# JLCPCB_MEG_SCHEM.net
KiCad netlist of a schematic drawn in EasyEDA
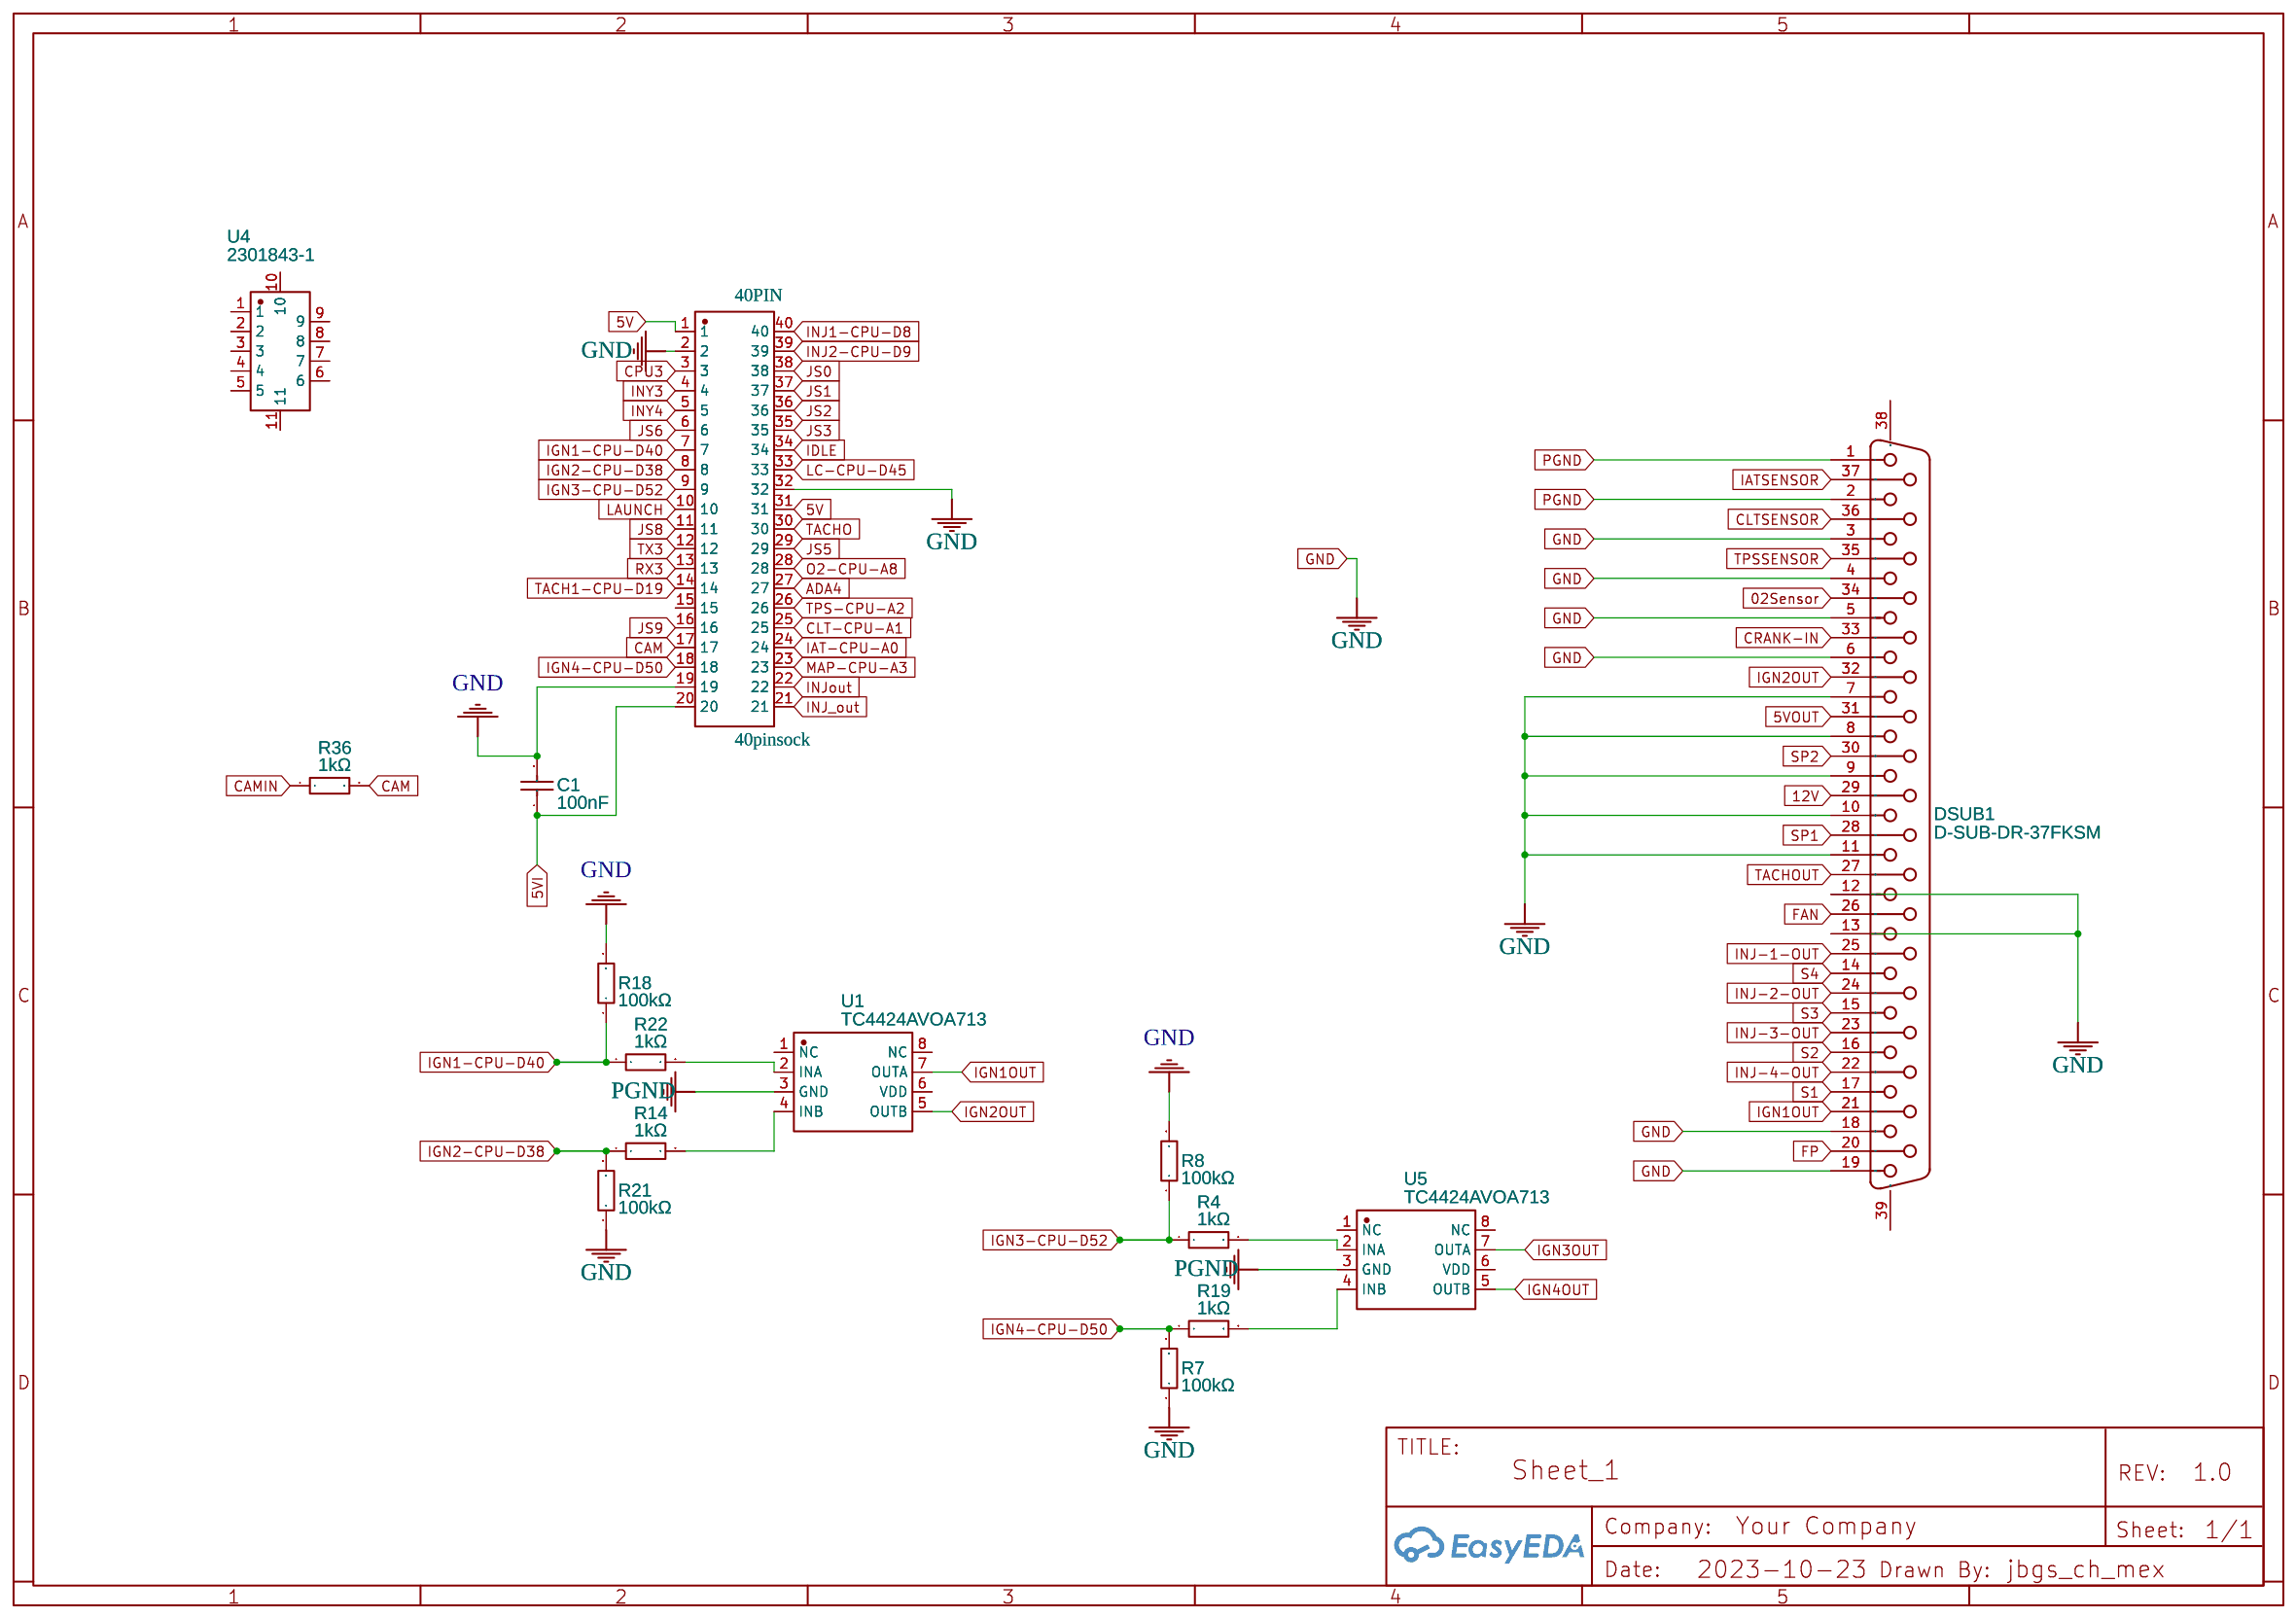
[diagram p0: Sheet_1]
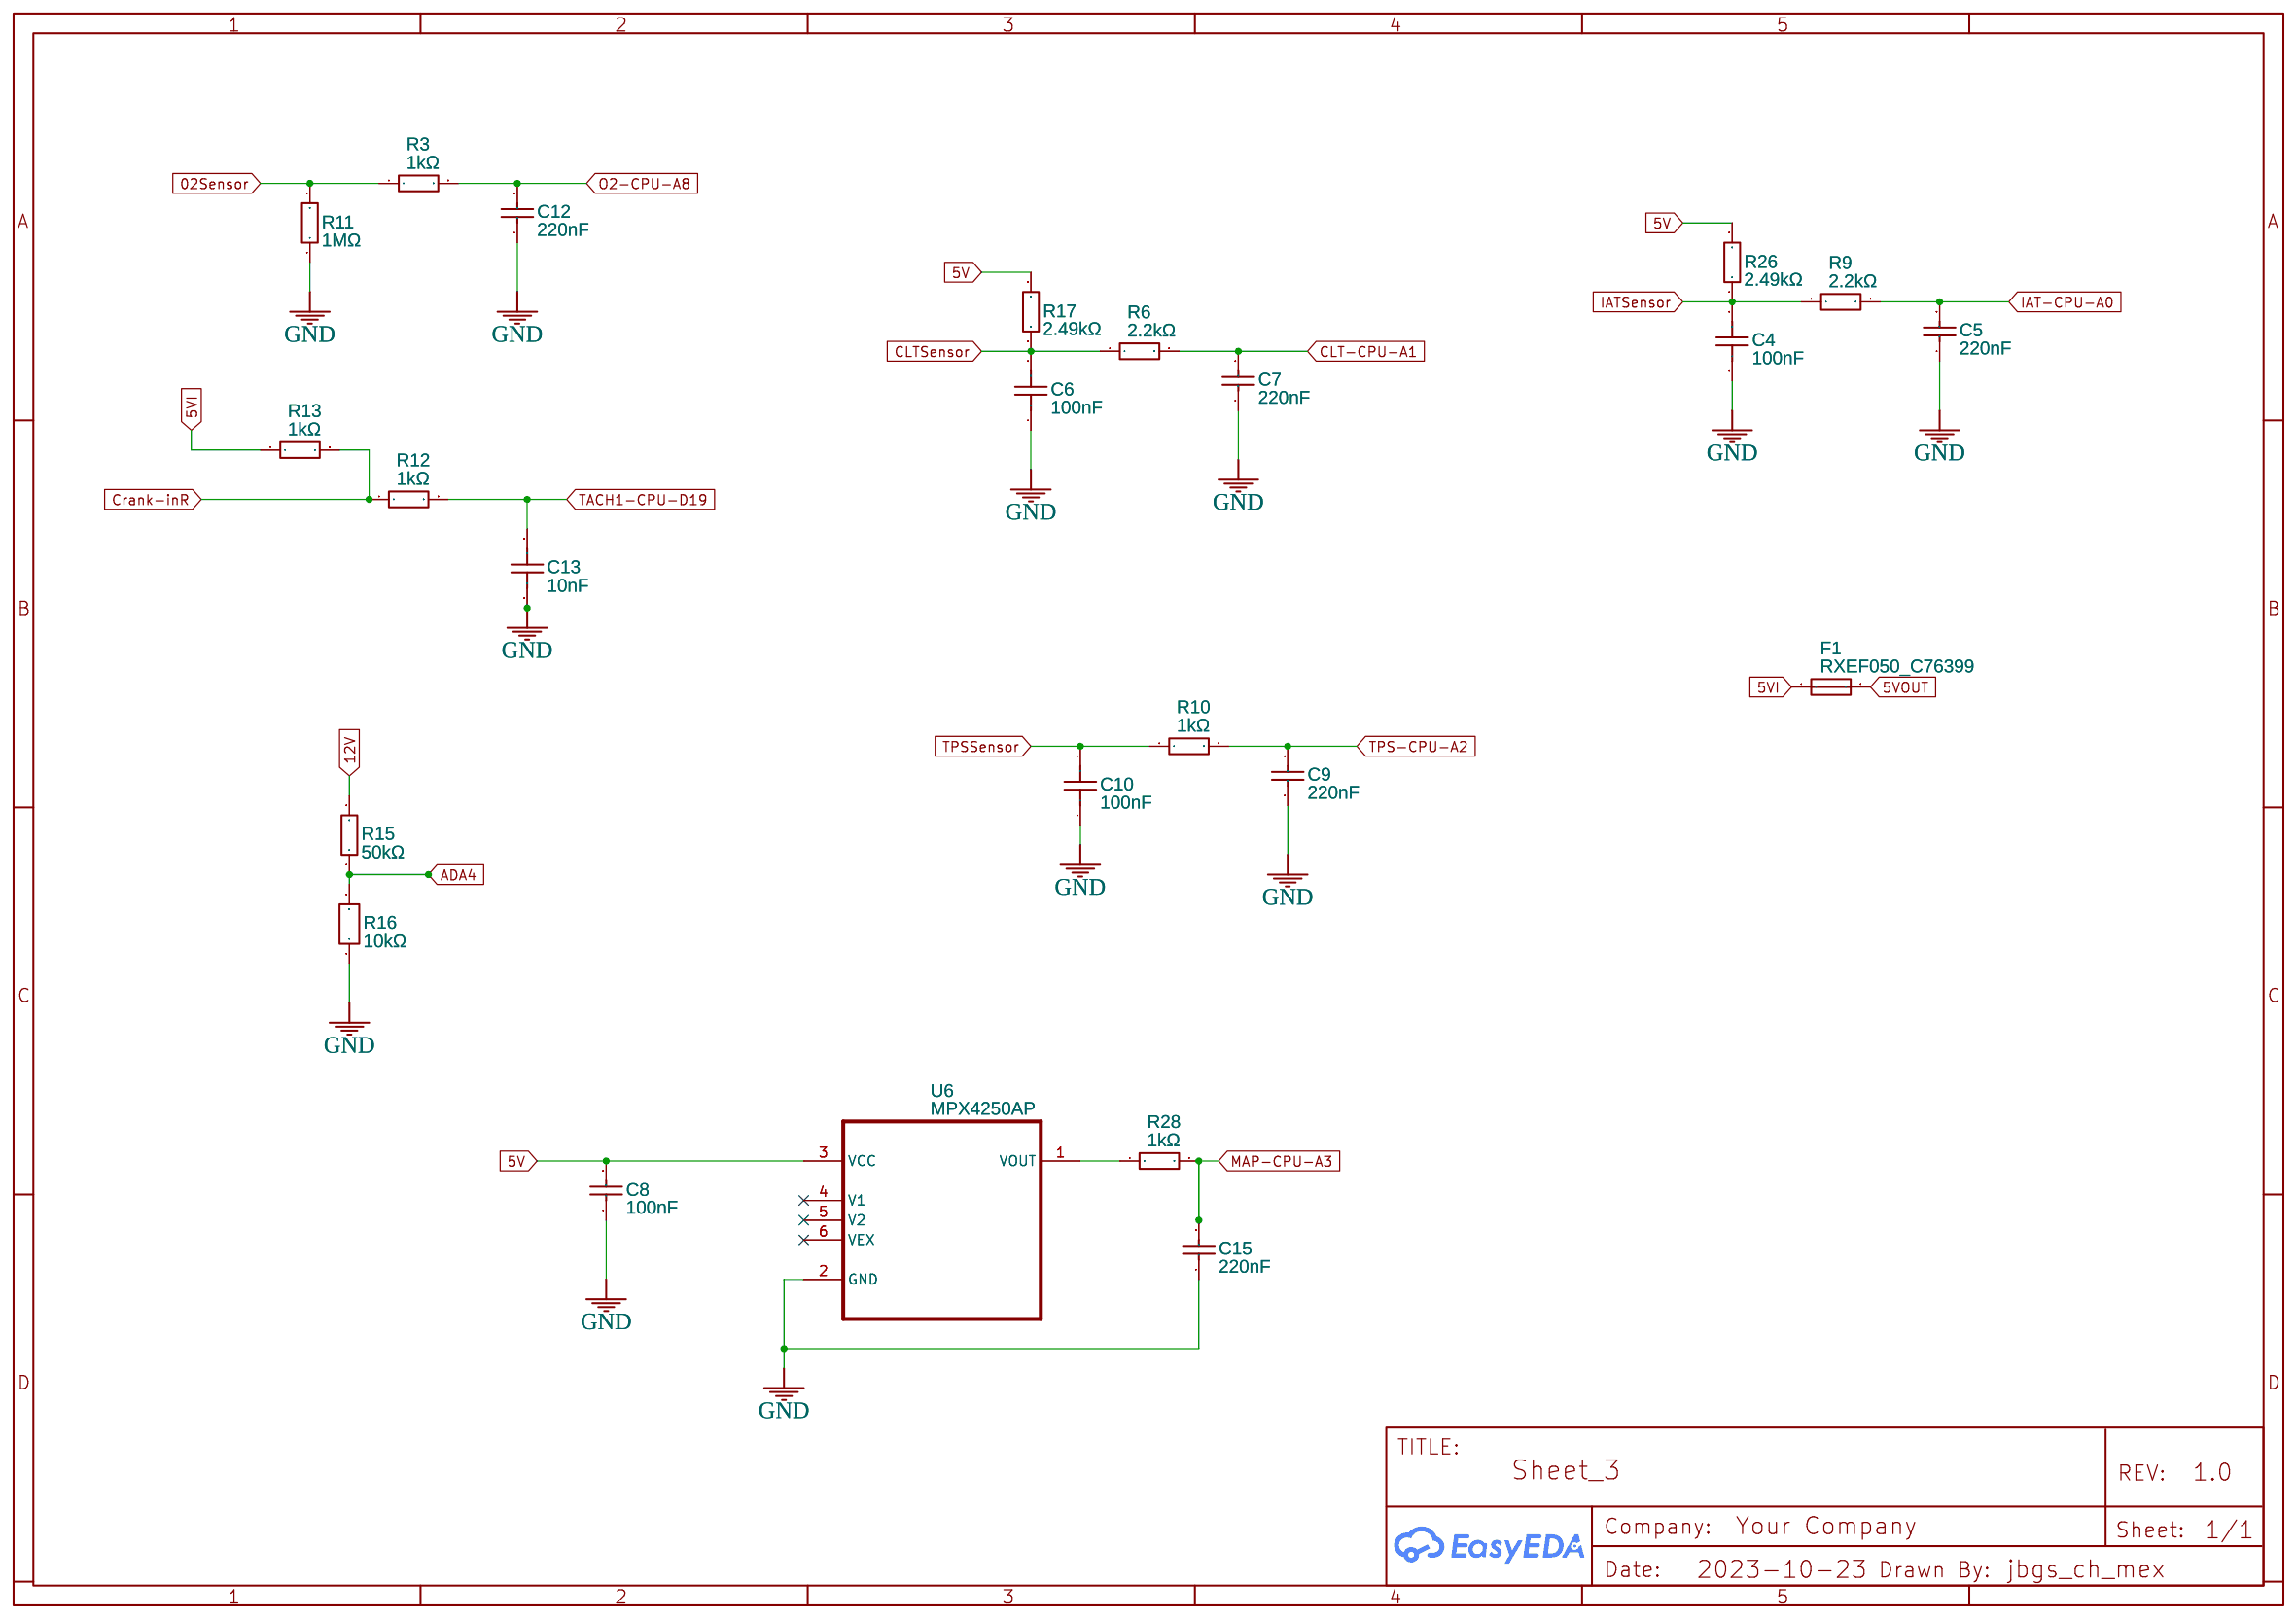
[diagram p1: Sheet_3]
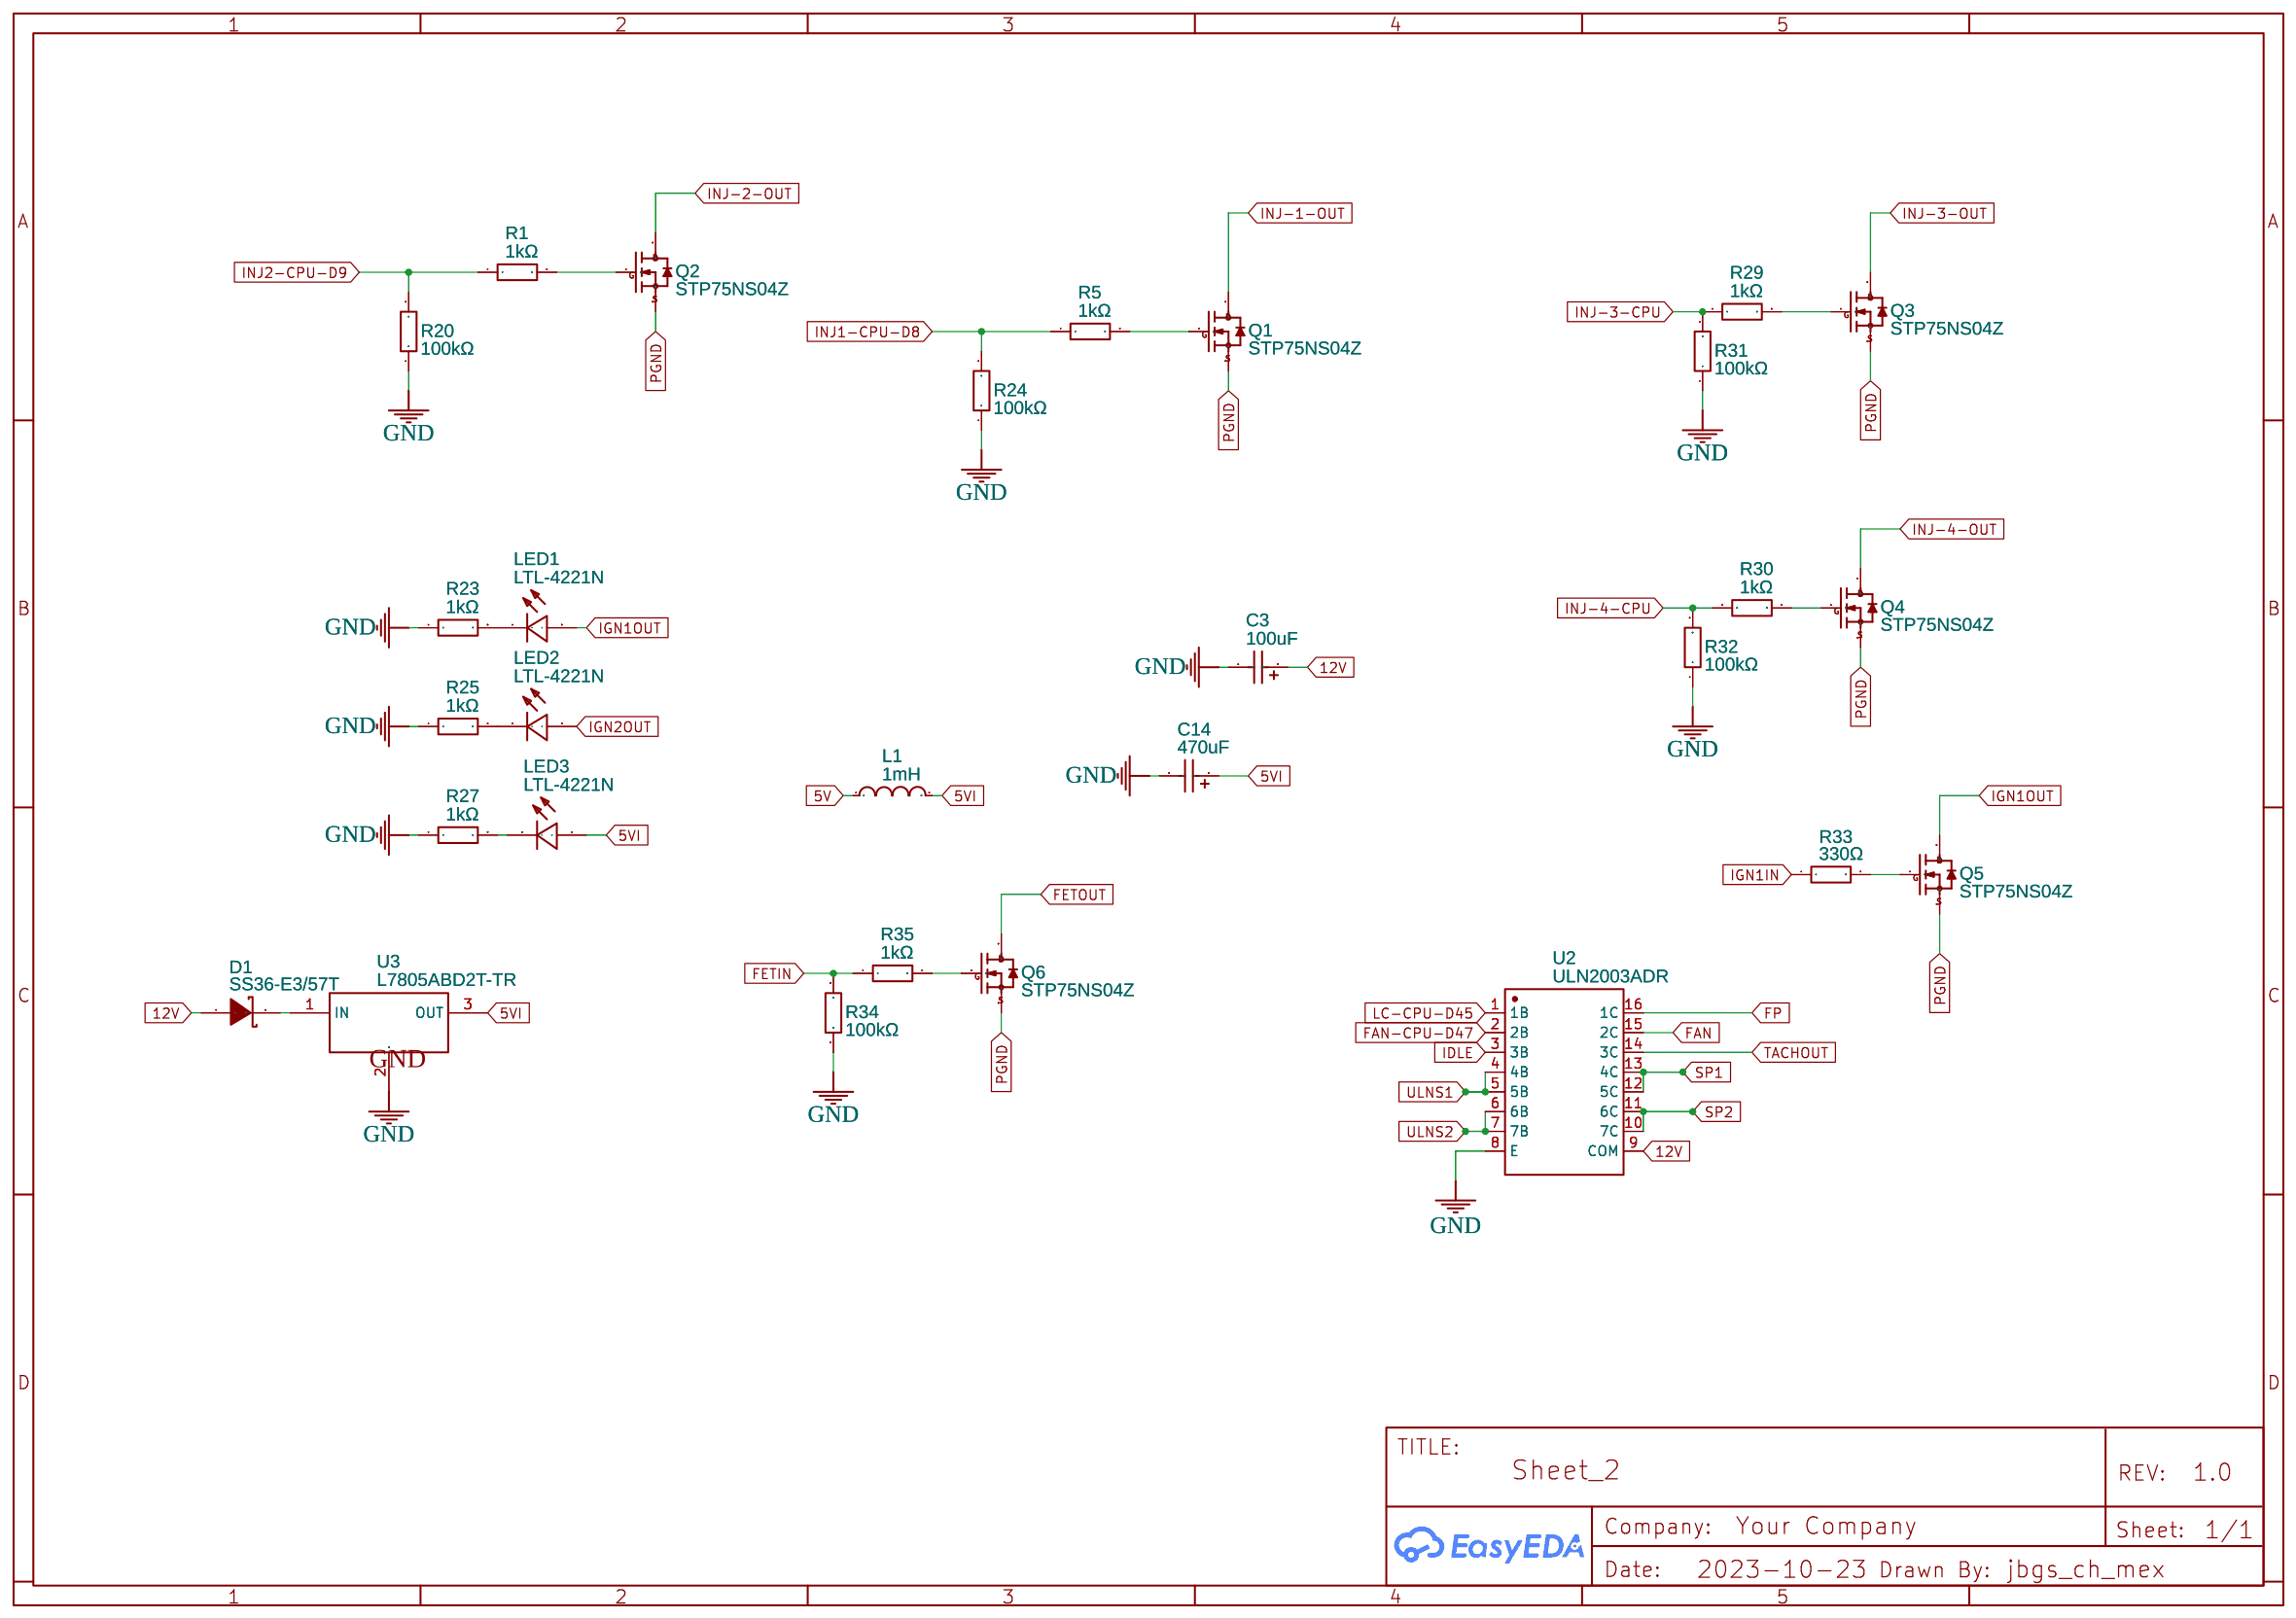
[diagram p2: Sheet_2]

(export (version "E")
  (design (tool "Eeschema 10.0.6"))
  (components
    (comp (ref "40PIN") (value "40pinsock") (libsource (lib "") (part "Unknown_365_-550")))
    (comp (ref "C1")
      (value "100nF")
      (fields
        (field (name "Manufacturer Part") "CC0805KRX7R9BB104")
        (field (name "Manufacturer") "YAGEO(国巨)")
      )
      (libsource (lib "") (part "CC0805KRX7R9BB104"))
    )
    (comp (ref "DSUB1")
      (value "D-SUB-DR-37FKSM")
      (fields (field (name "Manufacturer") "ZHOURI(洲日)"))
      (libsource (lib "") (part "D-SUB-DR-37FKSM"))
    )
    (comp (ref "R4")
      (value "1kΩ")
      (fields
        (field (name "Manufacturer Part") "0603WAF1001T5E")
        (field (name "Manufacturer") "UNI-ROYAL(厚声)")
      )
      (libsource (lib "") (part "0603WAF1001T5E"))
    )
    (comp (ref "R7")
      (value "100kΩ")
      (fields
        (field (name "Manufacturer Part") "0603WAF1003T5E")
        (field (name "Manufacturer") "UNI-ROYAL(厚声)")
      )
      (libsource (lib "") (part "0603WAF1003T5E"))
    )
    (comp (ref "R8")
      (value "100kΩ")
      (fields
        (field (name "Manufacturer Part") "0603WAF1003T5E")
        (field (name "Manufacturer") "UNI-ROYAL(厚声)")
      )
      (libsource (lib "") (part "0603WAF1003T5E"))
    )
    (comp (ref "R14")
      (value "1kΩ")
      (fields
        (field (name "Manufacturer Part") "0603WAF1001T5E")
        (field (name "Manufacturer") "UNI-ROYAL(厚声)")
      )
      (libsource (lib "") (part "0603WAF1001T5E"))
    )
    (comp (ref "R18")
      (value "100kΩ")
      (fields
        (field (name "Manufacturer Part") "0603WAF1003T5E")
        (field (name "Manufacturer") "UNI-ROYAL(厚声)")
      )
      (libsource (lib "") (part "0603WAF1003T5E"))
    )
    (comp (ref "R19")
      (value "1kΩ")
      (fields
        (field (name "Manufacturer Part") "0603WAF1001T5E")
        (field (name "Manufacturer") "UNI-ROYAL(厚声)")
      )
      (libsource (lib "") (part "0603WAF1001T5E"))
    )
    (comp (ref "R21")
      (value "100kΩ")
      (fields
        (field (name "Manufacturer Part") "0603WAF1003T5E")
        (field (name "Manufacturer") "UNI-ROYAL(厚声)")
      )
      (libsource (lib "") (part "0603WAF1003T5E"))
    )
    (comp (ref "R22")
      (value "1kΩ")
      (fields
        (field (name "Manufacturer Part") "0603WAF1001T5E")
        (field (name "Manufacturer") "UNI-ROYAL(厚声)")
      )
      (libsource (lib "") (part "0603WAF1001T5E"))
    )
    (comp (ref "R36")
      (value "1kΩ")
      (fields
        (field (name "Manufacturer Part") "0603WAF1001T5E")
        (field (name "Manufacturer") "UNI-ROYAL(厚声)")
      )
      (libsource (lib "") (part "0603WAF1001T5E"))
    )
    (comp (ref "U1")
      (value "TC4424AVOA713")
      (fields (field (name "Manufacturer") "MICROCHIP(美国微芯)"))
      (libsource (lib "") (part "TC4424AVOA713"))
    )
    (comp (ref "U4")
      (value "2301843-1")
      (fields (field (name "Manufacturer") "TE Connectivity(美国泰科)"))
      (libsource (lib "") (part "2301843-1"))
    )
    (comp (ref "U5")
      (value "TC4424AVOA713")
      (fields (field (name "Manufacturer") "MICROCHIP(美国微芯)"))
      (libsource (lib "") (part "TC4424AVOA713"))
    )
    (comp (ref "C4")
      (value "100nF")
      (fields
        (field (name "Manufacturer Part") "CC0603KRX7R9BB104")
        (field (name "Manufacturer") "YAGEO(国巨)")
      )
      (libsource (lib "") (part "CC0603KRX7R9BB104"))
    )
    (comp (ref "C5")
      (value "220nF")
      (fields
        (field (name "Manufacturer Part") "CL10B224KA8NNNC")
        (field (name "Manufacturer") "SAMSUNG(三星)")
      )
      (libsource (lib "") (part "CL10B224KA8NNNC"))
    )
    (comp (ref "C6")
      (value "100nF")
      (fields
        (field (name "Manufacturer Part") "CC0603KRX7R9BB104")
        (field (name "Manufacturer") "YAGEO(国巨)")
      )
      (libsource (lib "") (part "CC0603KRX7R9BB104"))
    )
    (comp (ref "C7")
      (value "220nF")
      (fields
        (field (name "Manufacturer Part") "CL10B224KA8NNNC")
        (field (name "Manufacturer") "SAMSUNG(三星)")
      )
      (libsource (lib "") (part "CL10B224KA8NNNC"))
    )
    (comp (ref "C8")
      (value "100nF")
      (fields
        (field (name "Manufacturer Part") "CC0805KRX7R9BB104")
        (field (name "Manufacturer") "YAGEO(国巨)")
      )
      (libsource (lib "") (part "CC0805KRX7R9BB104"))
    )
    (comp (ref "C9")
      (value "220nF")
      (fields
        (field (name "Manufacturer Part") "CL10B224KA8NNNC")
        (field (name "Manufacturer") "SAMSUNG(三星)")
      )
      (libsource (lib "") (part "CL10B224KA8NNNC"))
    )
    (comp (ref "C10")
      (value "100nF")
      (fields
        (field (name "Manufacturer Part") "CC0603KRX7R9BB104")
        (field (name "Manufacturer") "YAGEO(国巨)")
      )
      (libsource (lib "") (part "CC0603KRX7R9BB104"))
    )
    (comp (ref "C12")
      (value "220nF")
      (fields
        (field (name "Manufacturer Part") "CL10B224KA8NNNC")
        (field (name "Manufacturer") "SAMSUNG(三星)")
      )
      (libsource (lib "") (part "CL10B224KA8NNNC"))
    )
    (comp (ref "C13")
      (value "10nF")
      (fields (field (name "Manufacturer Part") "C0805C103K1RAC7800") (field (name "Manufacturer") "KEMET"))
      (libsource (lib "") (part "C0805C103K1RAC7800"))
    )
    (comp (ref "C15")
      (value "220nF")
      (fields
        (field (name "Manufacturer Part") "CL10B224KA8NNNC")
        (field (name "Manufacturer") "SAMSUNG(三星)")
      )
      (libsource (lib "") (part "CL10B224KA8NNNC"))
    )
    (comp (ref "F1")
      (value "RXEF050_C76399")
      (fields (field (name "Manufacturer Part") "RXEF050") (field (name "Manufacturer") "Littelfuse(美国力特)"))
      (libsource (lib "") (part "RXEF050_C76399"))
    )
    (comp (ref "R3")
      (value "1kΩ")
      (fields
        (field (name "Manufacturer Part") "0805W8F1001T5E")
        (field (name "Manufacturer") "UNI-ROYAL(厚声)")
      )
      (libsource (lib "") (part "0805W8F1001T5E"))
    )
    (comp (ref "R6")
      (value "2.2kΩ")
      (fields
        (field (name "Manufacturer Part") "0805W8F2201T5E")
        (field (name "Manufacturer") "UNI-ROYAL(厚声)")
      )
      (libsource (lib "") (part "0805W8F2201T5E"))
    )
    (comp (ref "R9")
      (value "2.2kΩ")
      (fields
        (field (name "Manufacturer Part") "0805W8F2201T5E")
        (field (name "Manufacturer") "UNI-ROYAL(厚声)")
      )
      (libsource (lib "") (part "0805W8F2201T5E"))
    )
    (comp (ref "R10")
      (value "1kΩ")
      (fields
        (field (name "Manufacturer Part") "0805W8F1001T5E")
        (field (name "Manufacturer") "UNI-ROYAL(厚声)")
      )
      (libsource (lib "") (part "0805W8F1001T5E"))
    )
    (comp (ref "R11")
      (value "1MΩ")
      (fields
        (field (name "Manufacturer Part") "0805W8F1004T5E")
        (field (name "Manufacturer") "UNI-ROYAL(厚声)")
      )
      (libsource (lib "") (part "0805W8F1004T5E"))
    )
    (comp (ref "R12")
      (value "1kΩ")
      (fields
        (field (name "Manufacturer Part") "0805W8F1001T5E")
        (field (name "Manufacturer") "UNI-ROYAL(厚声)")
      )
      (libsource (lib "") (part "0805W8F1001T5E"))
    )
    (comp (ref "R13")
      (value "1kΩ")
      (fields
        (field (name "Manufacturer Part") "0805W8F1001T5E")
        (field (name "Manufacturer") "UNI-ROYAL(厚声)")
      )
      (libsource (lib "") (part "0805W8F1001T5E"))
    )
    (comp (ref "R15")
      (value "50kΩ")
      (fields (field (name "Manufacturer Part") "AR03BTC5002A") (field (name "Manufacturer") "Viking(光颉)"))
      (libsource (lib "") (part "AR03BTC5002A"))
    )
    (comp (ref "R16")
      (value "10kΩ")
      (fields (field (name "Manufacturer Part") "SCR0603J10K") (field (name "Manufacturer") "VO(翔胜)"))
      (libsource (lib "") (part "SCR0603J10K"))
    )
    (comp (ref "R17")
      (value "2.49kΩ")
      (fields
        (field (name "Manufacturer Part") "0805W8F2491T5E")
        (field (name "Manufacturer") "UNI-ROYAL(厚声)")
      )
      (libsource (lib "") (part "0805W8F2491T5E"))
    )
    (comp (ref "R26")
      (value "2.49kΩ")
      (fields
        (field (name "Manufacturer Part") "0805W8F2491T5E")
        (field (name "Manufacturer") "UNI-ROYAL(厚声)")
      )
      (libsource (lib "") (part "0805W8F2491T5E"))
    )
    (comp (ref "R28")
      (value "1kΩ")
      (fields
        (field (name "Manufacturer Part") "0805W8F1001T5E")
        (field (name "Manufacturer") "UNI-ROYAL(厚声)")
      )
      (libsource (lib "") (part "0805W8F1001T5E"))
    )
    (comp (ref "U6")
      (value "MPX4250AP")
      (fields (field (name "Manufacturer Part") "?"))
      (libsource (lib "") (part "Unknown_470_-205"))
    )
    (comp (ref "C3")
      (value "100uF")
      (fields (field (name "Manufacturer Part") "TAJD107M020RNJ") (field (name "Manufacturer") "Kyocera AVX"))
      (libsource (lib "") (part "TAJD107M020RNJ"))
    )
    (comp (ref "C14")
      (value "470uF")
      (fields (field (name "Manufacturer Part") "T491D477K006AT") (field (name "Manufacturer") "KEMET(基美)"))
      (libsource (lib "") (part "T491D477K006AT"))
    )
    (comp (ref "D1")
      (value "SS36-E3/57T")
      (fields (field (name "Manufacturer") "VISHAY(威世)"))
      (libsource (lib "") (part "SS36-E3/57T"))
    )
    (comp (ref "L1")
      (value "1mH")
      (fields
        (field (name "Manufacturer Part") "SCDS127T-102M-N")
        (field (name "Manufacturer") "chilisin(奇力新)")
      )
      (libsource (lib "") (part "SCDS127T-102M-N"))
    )
    (comp (ref "LED1")
      (value "LTL-4221N")
      (fields (field (name "Manufacturer") "LITEON(光宝)"))
      (libsource (lib "") (part "LTL-4221N"))
    )
    (comp (ref "LED2")
      (value "LTL-4221N")
      (fields (field (name "Manufacturer") "LITEON(光宝)"))
      (libsource (lib "") (part "LTL-4221N"))
    )
    (comp (ref "LED3")
      (value "LTL-4221N")
      (fields (field (name "Manufacturer") "LITEON(光宝)"))
      (libsource (lib "") (part "LTL-4221N"))
    )
    (comp (ref "Q1")
      (value "STP75NS04Z")
      (fields (field (name "Manufacturer") "STMicroelectronics"))
      (libsource (lib "") (part "Unknown_605_-645"))
    )
    (comp (ref "Q2")
      (value "STP75NS04Z")
      (fields (field (name "Manufacturer") "STMicroelectronics"))
      (libsource (lib "") (part "Unknown_315_-675"))
    )
    (comp (ref "Q3")
      (value "STP75NS04Z")
      (fields (field (name "Manufacturer") "STMicroelectronics"))
      (libsource (lib "") (part "Unknown_930_-655"))
    )
    (comp (ref "Q4")
      (value "STP75NS04Z")
      (fields (field (name "Manufacturer") "STMicroelectronics"))
      (libsource (lib "") (part "Unknown_925_-505"))
    )
    (comp (ref "Q5")
      (value "STP75NS04Z")
      (fields (field (name "Manufacturer") "STMicroelectronics"))
      (libsource (lib "") (part "Unknown_965_-370"))
    )
    (comp (ref "Q6")
      (value "STP75NS04Z")
      (fields (field (name "Manufacturer") "STMicroelectronics"))
      (libsource (lib "") (part "Unknown_490_-320"))
    )
    (comp (ref "R1")
      (value "1kΩ")
      (fields
        (field (name "Manufacturer Part") "0805W8F1001T5E")
        (field (name "Manufacturer") "UNI-ROYAL(厚声)")
      )
      (libsource (lib "") (part "0805W8F1001T5E"))
    )
    (comp (ref "R5")
      (value "1kΩ")
      (fields
        (field (name "Manufacturer Part") "0805W8F1001T5E")
        (field (name "Manufacturer") "UNI-ROYAL(厚声)")
      )
      (libsource (lib "") (part "0805W8F1001T5E"))
    )
    (comp (ref "R20")
      (value "100kΩ")
      (fields
        (field (name "Manufacturer Part") "0805W8F1003T5E")
        (field (name "Manufacturer") "UNI-ROYAL(厚声)")
      )
      (libsource (lib "") (part "0805W8F1003T5E_C149504"))
    )
    (comp (ref "R23")
      (value "1kΩ")
      (fields
        (field (name "Manufacturer Part") "0805W8F1001T5E")
        (field (name "Manufacturer") "UNI-ROYAL(厚声)")
      )
      (libsource (lib "") (part "0805W8F1001T5E"))
    )
    (comp (ref "R24")
      (value "100kΩ")
      (fields
        (field (name "Manufacturer Part") "0805W8F1003T5E")
        (field (name "Manufacturer") "UNI-ROYAL(厚声)")
      )
      (libsource (lib "") (part "0805W8F1003T5E_C149504"))
    )
    (comp (ref "R25")
      (value "1kΩ")
      (fields
        (field (name "Manufacturer Part") "0805W8F1001T5E")
        (field (name "Manufacturer") "UNI-ROYAL(厚声)")
      )
      (libsource (lib "") (part "0805W8F1001T5E"))
    )
    (comp (ref "R27")
      (value "1kΩ")
      (fields
        (field (name "Manufacturer Part") "0805W8F1001T5E")
        (field (name "Manufacturer") "UNI-ROYAL(厚声)")
      )
      (libsource (lib "") (part "0805W8F1001T5E"))
    )
    (comp (ref "R29")
      (value "1kΩ")
      (fields
        (field (name "Manufacturer Part") "0805W8F1001T5E")
        (field (name "Manufacturer") "UNI-ROYAL(厚声)")
      )
      (libsource (lib "") (part "0805W8F1001T5E"))
    )
    (comp (ref "R30")
      (value "1kΩ")
      (fields
        (field (name "Manufacturer Part") "0805W8F1001T5E")
        (field (name "Manufacturer") "UNI-ROYAL(厚声)")
      )
      (libsource (lib "") (part "0805W8F1001T5E"))
    )
    (comp (ref "R31")
      (value "100kΩ")
      (fields
        (field (name "Manufacturer Part") "0805W8F1003T5E")
        (field (name "Manufacturer") "UNI-ROYAL(厚声)")
      )
      (libsource (lib "") (part "0805W8F1003T5E_C149504"))
    )
    (comp (ref "R32")
      (value "100kΩ")
      (fields
        (field (name "Manufacturer Part") "0805W8F1003T5E")
        (field (name "Manufacturer") "UNI-ROYAL(厚声)")
      )
      (libsource (lib "") (part "0805W8F1003T5E_C149504"))
    )
    (comp (ref "R33")
      (value "330Ω")
      (fields
        (field (name "Manufacturer Part") "0805W8F3300T5E")
        (field (name "Manufacturer") "UNI-ROYAL(厚声)")
      )
      (libsource (lib "") (part "0805W8F3300T5E"))
    )
    (comp (ref "R34")
      (value "100kΩ")
      (fields
        (field (name "Manufacturer Part") "0805W8F1003T5E")
        (field (name "Manufacturer") "UNI-ROYAL(厚声)")
      )
      (libsource (lib "") (part "0805W8F1003T5E_C149504"))
    )
    (comp (ref "R35")
      (value "1kΩ")
      (fields
        (field (name "Manufacturer Part") "0805W8F1001T5E")
        (field (name "Manufacturer") "UNI-ROYAL(厚声)")
      )
      (libsource (lib "") (part "0805W8F1001T5E"))
    )
    (comp (ref "U2")
      (value "ULN2003ADR")
      (fields (field (name "Manufacturer") "TI(德州仪器)"))
      (libsource (lib "") (part "ULN2003ADR"))
    )
    (comp (ref "U3")
      (value "L7805ABD2T-TR")
      (fields (field (name "Manufacturer") "ST(意法半导体)"))
      (libsource (lib "") (part "L7805ABD2T-TR"))
    )
  )
  (nets
    (net (code "1") (name "02Sensor") (class "Default")
      (node (ref "DSUB1") (pin "34") (pinfunction "23_34") (pintype "unspecified"))
      (node (ref "R11") (pin "2") (pinfunction "2_2") (pintype "input"))
      (node (ref "R3") (pin "1") (pinfunction "1_1") (pintype "input"))
    )
    (net (code "2") (name "5V") (class "Default")
      (node (ref "40PIN") (pin "1") (pinfunction "1_1") (pintype "unspecified"))
      (node (ref "40PIN") (pin "31") (pinfunction "31_31") (pintype "unspecified"))
      (node (ref "C8") (pin "2") (pinfunction "2_2") (pintype "input"))
      (node (ref "L1") (pin "1") (pinfunction "1_1") (pintype "unspecified"))
      (node (ref "R17") (pin "2") (pinfunction "2_2") (pintype "input"))
      (node (ref "R26") (pin "2") (pinfunction "2_2") (pintype "input"))
      (node (ref "U6") (pin "3") (pinfunction "VCC_3") (pintype "passive"))
    )
    (net (code "3") (name "5VI") (class "Default")
      (node (ref "40PIN") (pin "20") (pinfunction "20_20") (pintype "unspecified"))
      (node (ref "C1") (pin "1") (pinfunction "1_1") (pintype "input"))
      (node (ref "C14") (pin "1") (pinfunction "1_1") (pintype "input"))
      (node (ref "F1") (pin "1") (pinfunction "1_1") (pintype "unspecified"))
      (node (ref "L1") (pin "2") (pinfunction "2_2") (pintype "unspecified"))
      (node (ref "LED3") (pin "2") (pinfunction "+_2") (pintype "unspecified"))
      (node (ref "R13") (pin "1") (pinfunction "1_1") (pintype "input"))
      (node (ref "U3") (pin "3") (pinfunction "OUT_3") (pintype "passive"))
    )
    (net (code "4") (name "5VOUT") (class "Default")
      (node (ref "DSUB1") (pin "31") (pinfunction "26_31") (pintype "unspecified"))
      (node (ref "F1") (pin "2") (pinfunction "2_2") (pintype "unspecified"))
    )
    (net (code "5") (name "12V") (class "Default")
      (node (ref "C3") (pin "1") (pinfunction "1_1") (pintype "input"))
      (node (ref "D1") (pin "1") (pinfunction "A_1") (pintype "unspecified"))
      (node (ref "DSUB1") (pin "29") (pinfunction "28_29") (pintype "unspecified"))
      (node (ref "R15") (pin "2") (pinfunction "2_2") (pintype "unspecified"))
      (node (ref "U2") (pin "9") (pinfunction "COM_9") (pintype "unspecified"))
    )
    (net (code "6") (name "ADA4") (class "Default")
      (node (ref "40PIN") (pin "27") (pinfunction "27_27") (pintype "unspecified"))
      (node (ref "R15") (pin "1") (pinfunction "1_1") (pintype "unspecified"))
      (node (ref "R16") (pin "2") (pinfunction "2_2") (pintype "unspecified"))
    )
    (net (code "7") (name "CAM") (class "Default")
      (node (ref "40PIN") (pin "17") (pinfunction "17_17") (pintype "unspecified"))
      (node (ref "R36") (pin "2") (pinfunction "2_2") (pintype "input"))
    )
    (net (code "8") (name "CAMIN") (class "Default")
      (node (ref "R36") (pin "1") (pinfunction "1_1") (pintype "input"))
    )
    (net (code "9") (name "CLT-CPU-A1") (class "Default")
      (node (ref "40PIN") (pin "25") (pinfunction "25_25") (pintype "unspecified"))
      (node (ref "C7") (pin "2") (pinfunction "2_2") (pintype "input"))
      (node (ref "R6") (pin "2") (pinfunction "2_2") (pintype "input"))
    )
    (net (code "10") (name "CLTSENSOR") (class "Default")
      (node (ref "DSUB1") (pin "36") (pinfunction "21_36") (pintype "unspecified"))
    )
    (net (code "11") (name "CLTSensor") (class "Default")
      (node (ref "C6") (pin "2") (pinfunction "2_2") (pintype "unspecified"))
      (node (ref "R17") (pin "1") (pinfunction "1_1") (pintype "input"))
      (node (ref "R6") (pin "1") (pinfunction "1_1") (pintype "input"))
    )
    (net (code "12") (name "CPU3") (class "Default")
      (node (ref "40PIN") (pin "3") (pinfunction "3_3") (pintype "unspecified"))
    )
    (net (code "13") (name "CRANK-IN") (class "Default")
      (node (ref "DSUB1") (pin "33") (pinfunction "24_33") (pintype "unspecified"))
    )
    (net (code "14") (name "Crank-inR") (class "Default")
      (node (ref "R12") (pin "1") (pinfunction "1_1") (pintype "input"))
      (node (ref "R13") (pin "2") (pinfunction "2_2") (pintype "input"))
    )
    (net (code "15") (name "FAN") (class "Default")
      (node (ref "DSUB1") (pin "26") (pinfunction "31_26") (pintype "unspecified"))
      (node (ref "U2") (pin "15") (pinfunction "2C_15") (pintype "unspecified"))
    )
    (net (code "16") (name "FAN-CPU-D47") (class "Default")
      (node (ref "U2") (pin "2") (pinfunction "2B_2") (pintype "unspecified"))
    )
    (net (code "17") (name "FETIN") (class "Default")
      (node (ref "R34") (pin "2") (pinfunction "2_2") (pintype "unspecified"))
      (node (ref "R35") (pin "1") (pinfunction "1_1") (pintype "input"))
    )
    (net (code "18") (name "FETOUT") (class "Default")
      (node (ref "Q6") (pin "2") (pinfunction "D_2") (pintype "unspecified"))
    )
    (net (code "19") (name "FP") (class "Default")
      (node (ref "DSUB1") (pin "20") (pinfunction "37_20") (pintype "unspecified"))
      (node (ref "U2") (pin "16") (pinfunction "1C_16") (pintype "unspecified"))
    )
    (net (code "20") (name "GND") (class "Default")
      (node (ref "40PIN") (pin "19") (pinfunction "19_19") (pintype "unspecified"))
      (node (ref "40PIN") (pin "2") (pinfunction "2_2") (pintype "unspecified"))
      (node (ref "40PIN") (pin "32") (pinfunction "32_32") (pintype "unspecified"))
      (node (ref "C1") (pin "2") (pinfunction "2_2") (pintype "input"))
      (node (ref "C10") (pin "1") (pinfunction "1_1") (pintype "unspecified"))
      (node (ref "C12") (pin "1") (pinfunction "1_1") (pintype "input"))
      (node (ref "C13") (pin "1") (pinfunction "1_1") (pintype "unspecified"))
      (node (ref "C14") (pin "2") (pinfunction "2_2") (pintype "input"))
      (node (ref "C15") (pin "1") (pinfunction "1_1") (pintype "input"))
      (node (ref "C3") (pin "2") (pinfunction "2_2") (pintype "input"))
      (node (ref "C4") (pin "1") (pinfunction "1_1") (pintype "unspecified"))
      (node (ref "C5") (pin "1") (pinfunction "1_1") (pintype "input"))
      (node (ref "C6") (pin "1") (pinfunction "1_1") (pintype "unspecified"))
      (node (ref "C7") (pin "1") (pinfunction "1_1") (pintype "input"))
      (node (ref "C8") (pin "1") (pinfunction "1_1") (pintype "input"))
      (node (ref "C9") (pin "1") (pinfunction "1_1") (pintype "input"))
      (node (ref "DSUB1") (pin "10") (pinfunction "10_10") (pintype "input"))
      (node (ref "DSUB1") (pin "11") (pinfunction "11_11") (pintype "input"))
      (node (ref "DSUB1") (pin "12") (pinfunction "12_12") (pintype "input"))
      (node (ref "DSUB1") (pin "13") (pinfunction "13_13") (pintype "input"))
      (node (ref "DSUB1") (pin "18") (pinfunction "18_18") (pintype "unspecified"))
      (node (ref "DSUB1") (pin "19") (pinfunction "19_19") (pintype "unspecified"))
      (node (ref "DSUB1") (pin "3") (pinfunction "3_3") (pintype "input"))
      (node (ref "DSUB1") (pin "4") (pinfunction "4_4") (pintype "input"))
      (node (ref "DSUB1") (pin "5") (pinfunction "5_5") (pintype "input"))
      (node (ref "DSUB1") (pin "6") (pinfunction "6_6") (pintype "input"))
      (node (ref "DSUB1") (pin "7") (pinfunction "7_7") (pintype "input"))
      (node (ref "DSUB1") (pin "8") (pinfunction "8_8") (pintype "input"))
      (node (ref "DSUB1") (pin "9") (pinfunction "9_9") (pintype "input"))
      (node (ref "R11") (pin "1") (pinfunction "1_1") (pintype "input"))
      (node (ref "R16") (pin "1") (pinfunction "1_1") (pintype "unspecified"))
      (node (ref "R18") (pin "2") (pinfunction "2_2") (pintype "input"))
      (node (ref "R20") (pin "1") (pinfunction "1_1") (pintype "unspecified"))
      (node (ref "R21") (pin "1") (pinfunction "1_1") (pintype "input"))
      (node (ref "R23") (pin "1") (pinfunction "1_1") (pintype "input"))
      (node (ref "R24") (pin "1") (pinfunction "1_1") (pintype "unspecified"))
      (node (ref "R25") (pin "1") (pinfunction "1_1") (pintype "input"))
      (node (ref "R27") (pin "1") (pinfunction "1_1") (pintype "input"))
      (node (ref "R31") (pin "1") (pinfunction "1_1") (pintype "unspecified"))
      (node (ref "R32") (pin "1") (pinfunction "1_1") (pintype "unspecified"))
      (node (ref "R34") (pin "1") (pinfunction "1_1") (pintype "unspecified"))
      (node (ref "R7") (pin "1") (pinfunction "1_1") (pintype "input"))
      (node (ref "R8") (pin "2") (pinfunction "2_2") (pintype "input"))
      (node (ref "U2") (pin "8") (pinfunction "E_8") (pintype "unspecified"))
      (node (ref "U3") (pin "2") (pinfunction "GND_2") (pintype "passive"))
      (node (ref "U6") (pin "2") (pinfunction "GND_2") (pintype "passive"))
    )
    (net (code "21") (name "IAT-CPU-A0") (class "Default")
      (node (ref "40PIN") (pin "24") (pinfunction "24_24") (pintype "unspecified"))
      (node (ref "C5") (pin "2") (pinfunction "2_2") (pintype "input"))
      (node (ref "R9") (pin "2") (pinfunction "2_2") (pintype "input"))
    )
    (net (code "22") (name "IATSENSOR") (class "Default")
      (node (ref "DSUB1") (pin "37") (pinfunction "20_37") (pintype "unspecified"))
    )
    (net (code "23") (name "IATSensor") (class "Default")
      (node (ref "C4") (pin "2") (pinfunction "2_2") (pintype "unspecified"))
      (node (ref "R26") (pin "1") (pinfunction "1_1") (pintype "input"))
      (node (ref "R9") (pin "1") (pinfunction "1_1") (pintype "input"))
    )
    (net (code "24") (name "IDLE") (class "Default")
      (node (ref "40PIN") (pin "34") (pinfunction "34_34") (pintype "unspecified"))
      (node (ref "U2") (pin "3") (pinfunction "3B_3") (pintype "unspecified"))
    )
    (net (code "25") (name "IGN1-CPU-D40") (class "Default")
      (node (ref "40PIN") (pin "7") (pinfunction "7_7") (pintype "unspecified"))
      (node (ref "R18") (pin "1") (pinfunction "1_1") (pintype "input"))
      (node (ref "R22") (pin "1") (pinfunction "1_1") (pintype "input"))
    )
    (net (code "26") (name "IGN1IN") (class "Default")
      (node (ref "R33") (pin "1") (pinfunction "1_1") (pintype "input"))
    )
    (net (code "27") (name "IGN1OUT") (class "Default")
      (node (ref "DSUB1") (pin "21") (pinfunction "36_21") (pintype "unspecified"))
      (node (ref "LED1") (pin "2") (pinfunction "+_2") (pintype "unspecified"))
      (node (ref "Q5") (pin "2") (pinfunction "D_2") (pintype "unspecified"))
      (node (ref "U1") (pin "7") (pinfunction "OUTA_7") (pintype "unspecified"))
    )
    (net (code "28") (name "IGN2-CPU-D38") (class "Default")
      (node (ref "40PIN") (pin "8") (pinfunction "8_8") (pintype "unspecified"))
      (node (ref "R14") (pin "1") (pinfunction "1_1") (pintype "input"))
      (node (ref "R21") (pin "2") (pinfunction "2_2") (pintype "input"))
    )
    (net (code "29") (name "IGN2OUT") (class "Default")
      (node (ref "DSUB1") (pin "32") (pinfunction "25_32") (pintype "unspecified"))
      (node (ref "LED2") (pin "2") (pinfunction "+_2") (pintype "unspecified"))
      (node (ref "U1") (pin "5") (pinfunction "OUTB_5") (pintype "unspecified"))
    )
    (net (code "30") (name "IGN3-CPU-D52") (class "Default")
      (node (ref "40PIN") (pin "9") (pinfunction "9_9") (pintype "unspecified"))
      (node (ref "R4") (pin "1") (pinfunction "1_1") (pintype "input"))
      (node (ref "R8") (pin "1") (pinfunction "1_1") (pintype "input"))
    )
    (net (code "31") (name "IGN3OUT") (class "Default")
      (node (ref "U5") (pin "7") (pinfunction "OUTA_7") (pintype "unspecified"))
    )
    (net (code "32") (name "IGN4-CPU-D50") (class "Default")
      (node (ref "40PIN") (pin "18") (pinfunction "18_18") (pintype "unspecified"))
      (node (ref "R19") (pin "1") (pinfunction "1_1") (pintype "input"))
      (node (ref "R7") (pin "2") (pinfunction "2_2") (pintype "input"))
    )
    (net (code "33") (name "IGN4OUT") (class "Default")
      (node (ref "U5") (pin "5") (pinfunction "OUTB_5") (pintype "unspecified"))
    )
    (net (code "34") (name "INJ-1-OUT") (class "Default")
      (node (ref "DSUB1") (pin "25") (pinfunction "32_25") (pintype "unspecified"))
      (node (ref "Q1") (pin "2") (pinfunction "D_2") (pintype "unspecified"))
    )
    (net (code "35") (name "INJ-2-OUT") (class "Default")
      (node (ref "DSUB1") (pin "24") (pinfunction "33_24") (pintype "unspecified"))
      (node (ref "Q2") (pin "2") (pinfunction "D_2") (pintype "unspecified"))
    )
    (net (code "36") (name "INJ-3-CPU") (class "Default")
      (node (ref "R29") (pin "1") (pinfunction "1_1") (pintype "input"))
      (node (ref "R31") (pin "2") (pinfunction "2_2") (pintype "unspecified"))
    )
    (net (code "37") (name "INJ-3-OUT") (class "Default")
      (node (ref "DSUB1") (pin "23") (pinfunction "34_23") (pintype "unspecified"))
      (node (ref "Q3") (pin "2") (pinfunction "D_2") (pintype "unspecified"))
    )
    (net (code "38") (name "INJ-4-CPU") (class "Default")
      (node (ref "R30") (pin "1") (pinfunction "1_1") (pintype "input"))
      (node (ref "R32") (pin "2") (pinfunction "2_2") (pintype "unspecified"))
    )
    (net (code "39") (name "INJ-4-OUT") (class "Default")
      (node (ref "DSUB1") (pin "22") (pinfunction "35_22") (pintype "unspecified"))
      (node (ref "Q4") (pin "2") (pinfunction "D_2") (pintype "unspecified"))
    )
    (net (code "40") (name "INJ1-CPU-D8") (class "Default")
      (node (ref "40PIN") (pin "40") (pinfunction "40_40") (pintype "unspecified"))
      (node (ref "R24") (pin "2") (pinfunction "2_2") (pintype "unspecified"))
      (node (ref "R5") (pin "1") (pinfunction "1_1") (pintype "input"))
    )
    (net (code "41") (name "INJ2-CPU-D9") (class "Default")
      (node (ref "40PIN") (pin "39") (pinfunction "39_39") (pintype "unspecified"))
      (node (ref "R1") (pin "1") (pinfunction "1_1") (pintype "input"))
      (node (ref "R20") (pin "2") (pinfunction "2_2") (pintype "unspecified"))
    )
    (net (code "42") (name "INJ_out") (class "Default")
      (node (ref "40PIN") (pin "21") (pinfunction "21_21") (pintype "unspecified"))
    )
    (net (code "43") (name "INJout") (class "Default")
      (node (ref "40PIN") (pin "22") (pinfunction "22_22") (pintype "unspecified"))
    )
    (net (code "44") (name "INY3") (class "Default")
      (node (ref "40PIN") (pin "4") (pinfunction "4_4") (pintype "unspecified"))
    )
    (net (code "45") (name "INY4") (class "Default")
      (node (ref "40PIN") (pin "5") (pinfunction "5_5") (pintype "unspecified"))
    )
    (net (code "46") (name "JS0") (class "Default")
      (node (ref "40PIN") (pin "38") (pinfunction "38_38") (pintype "unspecified"))
    )
    (net (code "47") (name "JS1") (class "Default")
      (node (ref "40PIN") (pin "37") (pinfunction "37_37") (pintype "unspecified"))
    )
    (net (code "48") (name "JS2") (class "Default")
      (node (ref "40PIN") (pin "36") (pinfunction "36_36") (pintype "unspecified"))
    )
    (net (code "49") (name "JS3") (class "Default")
      (node (ref "40PIN") (pin "35") (pinfunction "35_35") (pintype "unspecified"))
    )
    (net (code "50") (name "JS5") (class "Default")
      (node (ref "40PIN") (pin "29") (pinfunction "29_29") (pintype "unspecified"))
    )
    (net (code "51") (name "JS6") (class "Default")
      (node (ref "40PIN") (pin "6") (pinfunction "6_6") (pintype "unspecified"))
    )
    (net (code "52") (name "JS8") (class "Default")
      (node (ref "40PIN") (pin "11") (pinfunction "11_11") (pintype "unspecified"))
    )
    (net (code "53") (name "JS9") (class "Default")
      (node (ref "40PIN") (pin "16") (pinfunction "16_16") (pintype "unspecified"))
    )
    (net (code "54") (name "LAUNCH") (class "Default")
      (node (ref "40PIN") (pin "10") (pinfunction "10_10") (pintype "unspecified"))
    )
    (net (code "55") (name "LC-CPU-D45") (class "Default")
      (node (ref "40PIN") (pin "33") (pinfunction "33_33") (pintype "unspecified"))
      (node (ref "U2") (pin "1") (pinfunction "1B_1") (pintype "unspecified"))
    )
    (net (code "56") (name "MAP-CPU-A3") (class "Default")
      (node (ref "40PIN") (pin "23") (pinfunction "23_23") (pintype "unspecified"))
      (node (ref "C15") (pin "2") (pinfunction "2_2") (pintype "input"))
      (node (ref "R28") (pin "2") (pinfunction "2_2") (pintype "input"))
    )
    (net (code "57") (name "Net-(D1-K)") (class "Default")
      (node (ref "D1") (pin "2") (pinfunction "K_2") (pintype "unspecified"))
      (node (ref "U3") (pin "1") (pinfunction "IN_1") (pintype "passive"))
    )
    (net (code "58") (name "Net-(LED1--)") (class "Default")
      (node (ref "LED1") (pin "1") (pinfunction "-_1") (pintype "unspecified"))
      (node (ref "R23") (pin "2") (pinfunction "2_2") (pintype "input"))
    )
    (net (code "59") (name "Net-(LED2--)") (class "Default")
      (node (ref "LED2") (pin "1") (pinfunction "-_1") (pintype "unspecified"))
      (node (ref "R25") (pin "2") (pinfunction "2_2") (pintype "input"))
    )
    (net (code "60") (name "Net-(LED3--)") (class "Default")
      (node (ref "LED3") (pin "1") (pinfunction "-_1") (pintype "unspecified"))
      (node (ref "R27") (pin "2") (pinfunction "2_2") (pintype "input"))
    )
    (net (code "61") (name "Net-(Q1-G)") (class "Default")
      (node (ref "Q1") (pin "1") (pinfunction "G_1") (pintype "unspecified"))
      (node (ref "R5") (pin "2") (pinfunction "2_2") (pintype "input"))
    )
    (net (code "62") (name "Net-(Q2-G)") (class "Default")
      (node (ref "Q2") (pin "1") (pinfunction "G_1") (pintype "unspecified"))
      (node (ref "R1") (pin "2") (pinfunction "2_2") (pintype "input"))
    )
    (net (code "63") (name "Net-(Q3-G)") (class "Default")
      (node (ref "Q3") (pin "1") (pinfunction "G_1") (pintype "unspecified"))
      (node (ref "R29") (pin "2") (pinfunction "2_2") (pintype "input"))
    )
    (net (code "64") (name "Net-(Q4-G)") (class "Default")
      (node (ref "Q4") (pin "1") (pinfunction "G_1") (pintype "unspecified"))
      (node (ref "R30") (pin "2") (pinfunction "2_2") (pintype "input"))
    )
    (net (code "65") (name "Net-(Q5-G)") (class "Default")
      (node (ref "Q5") (pin "1") (pinfunction "G_1") (pintype "unspecified"))
      (node (ref "R33") (pin "2") (pinfunction "2_2") (pintype "input"))
    )
    (net (code "66") (name "Net-(Q6-G)") (class "Default")
      (node (ref "Q6") (pin "1") (pinfunction "G_1") (pintype "unspecified"))
      (node (ref "R35") (pin "2") (pinfunction "2_2") (pintype "input"))
    )
    (net (code "67") (name "Net-(U1-INA)") (class "Default")
      (node (ref "R22") (pin "2") (pinfunction "2_2") (pintype "input"))
      (node (ref "U1") (pin "2") (pinfunction "INA_2") (pintype "unspecified"))
    )
    (net (code "68") (name "Net-(U1-INB)") (class "Default")
      (node (ref "R14") (pin "2") (pinfunction "2_2") (pintype "input"))
      (node (ref "U1") (pin "4") (pinfunction "INB_4") (pintype "unspecified"))
    )
    (net (code "69") (name "Net-(U5-INA)") (class "Default")
      (node (ref "R4") (pin "2") (pinfunction "2_2") (pintype "input"))
      (node (ref "U5") (pin "2") (pinfunction "INA_2") (pintype "unspecified"))
    )
    (net (code "70") (name "Net-(U5-INB)") (class "Default")
      (node (ref "R19") (pin "2") (pinfunction "2_2") (pintype "input"))
      (node (ref "U5") (pin "4") (pinfunction "INB_4") (pintype "unspecified"))
    )
    (net (code "71") (name "Net-(U6-VOUT)") (class "Default")
      (node (ref "R28") (pin "1") (pinfunction "1_1") (pintype "input"))
      (node (ref "U6") (pin "1") (pinfunction "VOUT_1") (pintype "output"))
    )
    (net (code "72") (name "O2-CPU-A8") (class "Default")
      (node (ref "40PIN") (pin "28") (pinfunction "28_28") (pintype "unspecified"))
      (node (ref "C12") (pin "2") (pinfunction "2_2") (pintype "input"))
      (node (ref "R3") (pin "2") (pinfunction "2_2") (pintype "input"))
    )
    (net (code "73") (name "PGND") (class "Default")
      (node (ref "DSUB1") (pin "1") (pinfunction "1_1") (pintype "input"))
      (node (ref "DSUB1") (pin "2") (pinfunction "2_2") (pintype "input"))
      (node (ref "Q1") (pin "3") (pinfunction "S_3") (pintype "unspecified"))
      (node (ref "Q2") (pin "3") (pinfunction "S_3") (pintype "unspecified"))
      (node (ref "Q3") (pin "3") (pinfunction "S_3") (pintype "unspecified"))
      (node (ref "Q4") (pin "3") (pinfunction "S_3") (pintype "unspecified"))
      (node (ref "Q5") (pin "3") (pinfunction "S_3") (pintype "unspecified"))
      (node (ref "Q6") (pin "3") (pinfunction "S_3") (pintype "unspecified"))
      (node (ref "U1") (pin "3") (pinfunction "GND_3") (pintype "unspecified"))
      (node (ref "U5") (pin "3") (pinfunction "GND_3") (pintype "unspecified"))
    )
    (net (code "74") (name "RX3") (class "Default")
      (node (ref "40PIN") (pin "13") (pinfunction "13_13") (pintype "unspecified"))
    )
    (net (code "75") (name "S1") (class "Default")
      (node (ref "DSUB1") (pin "17") (pinfunction "17_17") (pintype "unspecified"))
    )
    (net (code "76") (name "S2") (class "Default")
      (node (ref "DSUB1") (pin "16") (pinfunction "16_16") (pintype "unspecified"))
    )
    (net (code "77") (name "S3") (class "Default")
      (node (ref "DSUB1") (pin "15") (pinfunction "15_15") (pintype "input"))
    )
    (net (code "78") (name "S4") (class "Default")
      (node (ref "DSUB1") (pin "14") (pinfunction "14_14") (pintype "input"))
    )
    (net (code "79") (name "SP1") (class "Default")
      (node (ref "DSUB1") (pin "28") (pinfunction "29_28") (pintype "unspecified"))
      (node (ref "U2") (pin "12") (pinfunction "5C_12") (pintype "unspecified"))
      (node (ref "U2") (pin "13") (pinfunction "4C_13") (pintype "unspecified"))
    )
    (net (code "80") (name "SP2") (class "Default")
      (node (ref "DSUB1") (pin "30") (pinfunction "27_30") (pintype "unspecified"))
      (node (ref "U2") (pin "10") (pinfunction "7C_10") (pintype "unspecified"))
      (node (ref "U2") (pin "11") (pinfunction "6C_11") (pintype "unspecified"))
    )
    (net (code "81") (name "TACH1-CPU-D19") (class "Default")
      (node (ref "40PIN") (pin "14") (pinfunction "14_14") (pintype "unspecified"))
      (node (ref "C13") (pin "2") (pinfunction "2_2") (pintype "unspecified"))
      (node (ref "R12") (pin "2") (pinfunction "2_2") (pintype "input"))
    )
    (net (code "82") (name "TACHO") (class "Default")
      (node (ref "40PIN") (pin "30") (pinfunction "30_30") (pintype "unspecified"))
    )
    (net (code "83") (name "TACHOUT") (class "Default")
      (node (ref "DSUB1") (pin "27") (pinfunction "30_27") (pintype "unspecified"))
      (node (ref "U2") (pin "14") (pinfunction "3C_14") (pintype "unspecified"))
    )
    (net (code "84") (name "TPS-CPU-A2") (class "Default")
      (node (ref "40PIN") (pin "26") (pinfunction "26_26") (pintype "unspecified"))
      (node (ref "C9") (pin "2") (pinfunction "2_2") (pintype "input"))
      (node (ref "R10") (pin "2") (pinfunction "2_2") (pintype "input"))
    )
    (net (code "85") (name "TPSSENSOR") (class "Default")
      (node (ref "DSUB1") (pin "35") (pinfunction "22_35") (pintype "unspecified"))
    )
    (net (code "86") (name "TPSSensor") (class "Default")
      (node (ref "C10") (pin "2") (pinfunction "2_2") (pintype "unspecified"))
      (node (ref "R10") (pin "1") (pinfunction "1_1") (pintype "input"))
    )
    (net (code "87") (name "TX3") (class "Default")
      (node (ref "40PIN") (pin "12") (pinfunction "12_12") (pintype "unspecified"))
    )
    (net (code "88") (name "ULNS1") (class "Default")
      (node (ref "U2") (pin "4") (pinfunction "4B_4") (pintype "unspecified"))
      (node (ref "U2") (pin "5") (pinfunction "5B_5") (pintype "unspecified"))
    )
    (net (code "89") (name "ULNS2") (class "Default")
      (node (ref "U2") (pin "6") (pinfunction "6B_6") (pintype "unspecified"))
      (node (ref "U2") (pin "7") (pinfunction "7B_7") (pintype "unspecified"))
    )
    (net (code "90") (name "unconnected-(40PIN-Pad15)") (class "Default")
      (node (ref "40PIN") (pin "15") (pinfunction "15_15") (pintype "unspecified"))
    )
    (net (code "91") (name "unconnected-(DSUB1-Pad38)") (class "Default")
      (node (ref "DSUB1") (pin "38") (pinfunction "38_38") (pintype "unspecified"))
    )
    (net (code "92") (name "unconnected-(DSUB1-Pad39)") (class "Default")
      (node (ref "DSUB1") (pin "39") (pinfunction "39_39") (pintype "unspecified"))
    )
    (net (code "93") (name "unconnected-(U1-NC-Pad1)") (class "Default")
      (node (ref "U1") (pin "1") (pinfunction "NC_1") (pintype "unspecified"))
    )
    (net (code "94") (name "unconnected-(U1-NC-Pad8)") (class "Default")
      (node (ref "U1") (pin "8") (pinfunction "NC_8") (pintype "unspecified"))
    )
    (net (code "95") (name "unconnected-(U1-VDD-Pad6)") (class "Default")
      (node (ref "U1") (pin "6") (pinfunction "VDD_6") (pintype "unspecified"))
    )
    (net (code "96") (name "unconnected-(U4-Pad1)") (class "Default")
      (node (ref "U4") (pin "1") (pinfunction "1_1") (pintype "unspecified"))
    )
    (net (code "97") (name "unconnected-(U4-Pad2)") (class "Default")
      (node (ref "U4") (pin "2") (pinfunction "2_2") (pintype "unspecified"))
    )
    (net (code "98") (name "unconnected-(U4-Pad3)") (class "Default")
      (node (ref "U4") (pin "3") (pinfunction "3_3") (pintype "unspecified"))
    )
    (net (code "99") (name "unconnected-(U4-Pad4)") (class "Default")
      (node (ref "U4") (pin "4") (pinfunction "4_4") (pintype "unspecified"))
    )
    (net (code "100") (name "unconnected-(U4-Pad5)") (class "Default")
      (node (ref "U4") (pin "5") (pinfunction "5_5") (pintype "unspecified"))
    )
    (net (code "101") (name "unconnected-(U4-Pad6)") (class "Default")
      (node (ref "U4") (pin "6") (pinfunction "6_6") (pintype "unspecified"))
    )
    (net (code "102") (name "unconnected-(U4-Pad7)") (class "Default")
      (node (ref "U4") (pin "7") (pinfunction "7_7") (pintype "unspecified"))
    )
    (net (code "103") (name "unconnected-(U4-Pad8)") (class "Default")
      (node (ref "U4") (pin "8") (pinfunction "8_8") (pintype "unspecified"))
    )
    (net (code "104") (name "unconnected-(U4-Pad9)") (class "Default")
      (node (ref "U4") (pin "9") (pinfunction "9_9") (pintype "unspecified"))
    )
    (net (code "105") (name "unconnected-(U4-Pad10)") (class "Default")
      (node (ref "U4") (pin "10") (pinfunction "10_10") (pintype "unspecified"))
    )
    (net (code "106") (name "unconnected-(U4-Pad11)") (class "Default")
      (node (ref "U4") (pin "11") (pinfunction "11_11") (pintype "unspecified"))
    )
    (net (code "107") (name "unconnected-(U5-NC-Pad1)") (class "Default")
      (node (ref "U5") (pin "1") (pinfunction "NC_1") (pintype "unspecified"))
    )
    (net (code "108") (name "unconnected-(U5-NC-Pad8)") (class "Default")
      (node (ref "U5") (pin "8") (pinfunction "NC_8") (pintype "unspecified"))
    )
    (net (code "109") (name "unconnected-(U5-VDD-Pad6)") (class "Default")
      (node (ref "U5") (pin "6") (pinfunction "VDD_6") (pintype "unspecified"))
    )
    (net (code "110") (name "unconnected-(U6-V1-Pad4)") (class "Default")
      (node (ref "U6") (pin "4") (pinfunction "V1_4") (pintype "input+no_connect"))
    )
    (net (code "111") (name "unconnected-(U6-V2-Pad5)") (class "Default")
      (node (ref "U6") (pin "5") (pinfunction "V2_5") (pintype "input+no_connect"))
    )
    (net (code "112") (name "unconnected-(U6-VEX-Pad6)") (class "Default")
      (node (ref "U6") (pin "6") (pinfunction "VEX_6") (pintype "unspecified+no_connect"))
    )
  )
)
